# PowerManagementBoard_LabelsAdj.net
KiCad netlist of a schematic drawn in EAGLE
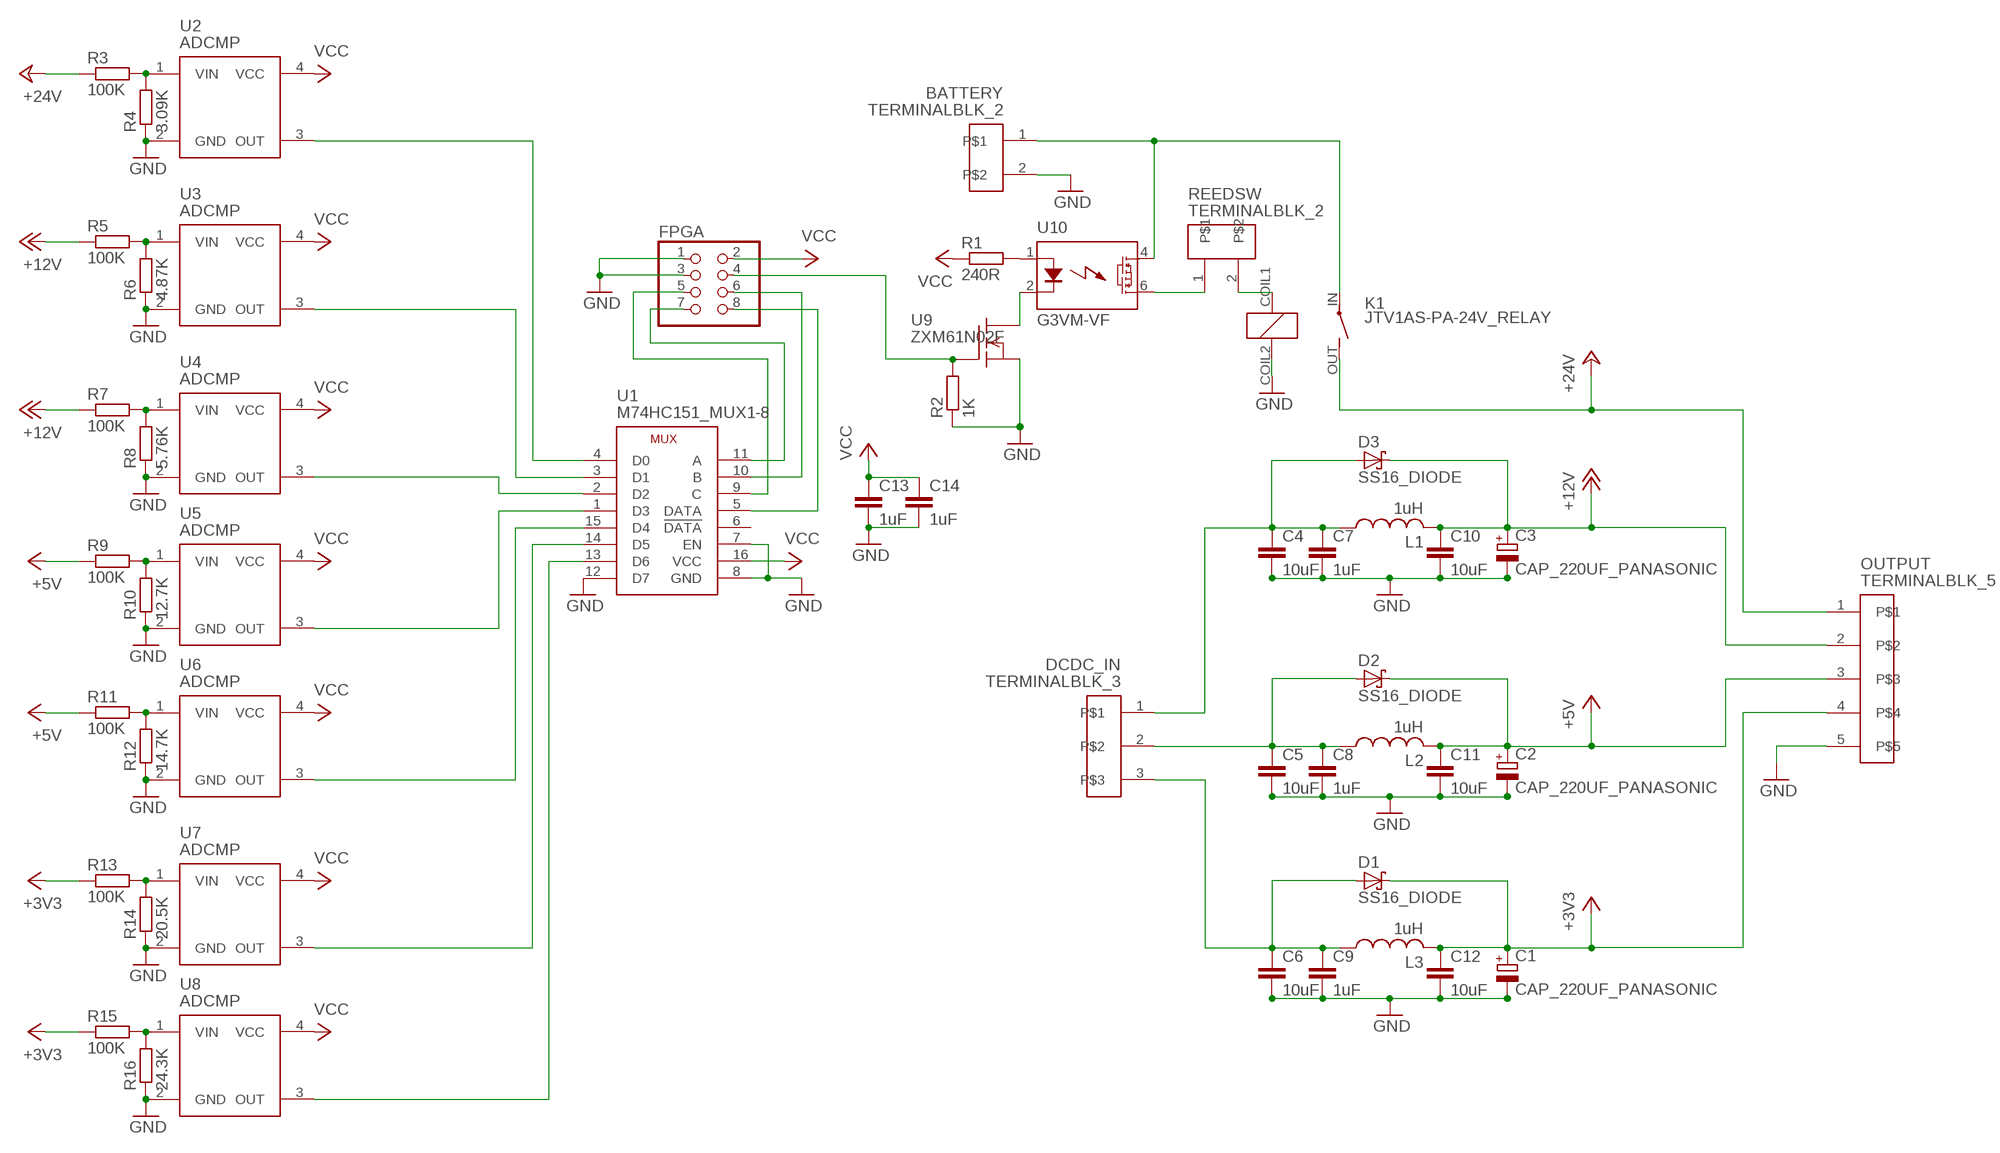
[diagram p0: schematic, sheet 1]

(export (version "E")
  (design (tool "Eeschema 10.0.6"))
  (components
    (comp (ref "BATTERY")
      (value "TERMINALBLK_2")
      (footprint "eagle-import:TERMINAL_BLK-2")
      (libsource (lib "eagle-import") (part "TERMINALBLK_2"))
    )
    (comp (ref "C1")
      (value "CAP_220UF_PANASONIC")
      (footprint "eagle-import:CAP_220UF_PANASONIC")
      (libsource (lib "eagle-import") (part "CAP_220UF_PANASONIC"))
    )
    (comp (ref "C2")
      (value "CAP_220UF_PANASONIC")
      (footprint "eagle-import:CAP_220UF_PANASONIC")
      (libsource (lib "eagle-import") (part "CAP_220UF_PANASONIC"))
    )
    (comp (ref "C3")
      (value "CAP_220UF_PANASONIC")
      (footprint "eagle-import:CAP_220UF_PANASONIC")
      (libsource (lib "eagle-import") (part "CAP_220UF_PANASONIC"))
    )
    (comp (ref "C4")
      (value "10uF")
      (footprint "eagle-import:C1206")
      (libsource (lib "eagle-import") (part "C-EUC1206"))
    )
    (comp (ref "C5")
      (value "10uF")
      (footprint "eagle-import:C1206")
      (libsource (lib "eagle-import") (part "C-EUC1206"))
    )
    (comp (ref "C6")
      (value "10uF")
      (footprint "eagle-import:C1206")
      (libsource (lib "eagle-import") (part "C-EUC1206"))
    )
    (comp (ref "C7")
      (value "1uF")
      (footprint "eagle-import:C1206")
      (libsource (lib "eagle-import") (part "C-EUC1206"))
    )
    (comp (ref "C8")
      (value "1uF")
      (footprint "eagle-import:C1206")
      (libsource (lib "eagle-import") (part "C-EUC1206"))
    )
    (comp (ref "C9")
      (value "1uF")
      (footprint "eagle-import:C1206")
      (libsource (lib "eagle-import") (part "C-EUC1206"))
    )
    (comp (ref "C10")
      (value "10uF")
      (footprint "eagle-import:C1206")
      (libsource (lib "eagle-import") (part "C-EUC1206"))
    )
    (comp (ref "C11")
      (value "10uF")
      (footprint "eagle-import:C1206")
      (libsource (lib "eagle-import") (part "C-EUC1206"))
    )
    (comp (ref "C12")
      (value "10uF")
      (footprint "eagle-import:C1206")
      (libsource (lib "eagle-import") (part "C-EUC1206"))
    )
    (comp (ref "C13")
      (value "1uF")
      (footprint "eagle-import:C1206")
      (libsource (lib "eagle-import") (part "C-EUC1206"))
    )
    (comp (ref "C14")
      (value "1uF")
      (footprint "eagle-import:C1206")
      (libsource (lib "eagle-import") (part "C-EUC1206"))
    )
    (comp (ref "D1")
      (value "SS16_DIODE")
      (footprint "eagle-import:DO214AC")
      (libsource (lib "eagle-import") (part "SS16_DIODE"))
    )
    (comp (ref "D2")
      (value "SS16_DIODE")
      (footprint "eagle-import:DO214AC")
      (libsource (lib "eagle-import") (part "SS16_DIODE"))
    )
    (comp (ref "D3")
      (value "SS16_DIODE")
      (footprint "eagle-import:DO214AC")
      (libsource (lib "eagle-import") (part "SS16_DIODE"))
    )
    (comp (ref "DCDC_IN")
      (value "TERMINALBLK_3")
      (footprint "eagle-import:TERMINAL_BLK-3")
      (libsource (lib "eagle-import") (part "TERMINALBLK_3"))
    )
    (comp (ref "FPGA")
      (value "PINHD-2X4")
      (footprint "eagle-import:2X04")
      (libsource (lib "eagle-import") (part "PINHD-2X4"))
    )
    (comp (ref "K1")
      (value "JTV1AS-PA-24V_RELAY")
      (footprint "eagle-import:JTV-RELAY_FORM1A")
      (libsource (lib "eagle-import") (part "JTV1AS-PA-24V_RELAY"))
    )
    (comp (ref "L1")
      (value "1uH")
      (footprint "eagle-import:CHOKE_WE-HCC_8070")
      (libsource (lib "eagle-import") (part "CHOKE_1UH_WE-HCC_8070"))
    )
    (comp (ref "L2")
      (value "1uH")
      (footprint "eagle-import:CHOKE_WE-HCC_8070")
      (libsource (lib "eagle-import") (part "CHOKE_1UH_WE-HCC_8070"))
    )
    (comp (ref "L3")
      (value "1uH")
      (footprint "eagle-import:CHOKE_WE-HCC_8070")
      (libsource (lib "eagle-import") (part "CHOKE_1UH_WE-HCC_8070"))
    )
    (comp (ref "OUTPUT")
      (value "TERMINALBLK_5")
      (footprint "eagle-import:TERMINAL_BLK-5")
      (libsource (lib "eagle-import") (part "TERMINALBLK_5"))
    )
    (comp (ref "R1")
      (value "240R")
      (footprint "eagle-import:R0603")
      (libsource (lib "eagle-import") (part "R-EU_R0603"))
    )
    (comp (ref "R2")
      (value "1K")
      (footprint "eagle-import:R0603")
      (libsource (lib "eagle-import") (part "R-EU_R0603"))
    )
    (comp (ref "R3")
      (value "100K")
      (footprint "eagle-import:R0603")
      (libsource (lib "eagle-import") (part "R-EU_R0603"))
    )
    (comp (ref "R4")
      (value "3.09K")
      (footprint "eagle-import:R0603")
      (libsource (lib "eagle-import") (part "R-EU_R0603"))
    )
    (comp (ref "R5")
      (value "100K")
      (footprint "eagle-import:R0603")
      (libsource (lib "eagle-import") (part "R-EU_R0603"))
    )
    (comp (ref "R6")
      (value "4.87K")
      (footprint "eagle-import:R0603")
      (libsource (lib "eagle-import") (part "R-EU_R0603"))
    )
    (comp (ref "R7")
      (value "100K")
      (footprint "eagle-import:R0603")
      (libsource (lib "eagle-import") (part "R-EU_R0603"))
    )
    (comp (ref "R8")
      (value "5.76K")
      (footprint "eagle-import:R0603")
      (libsource (lib "eagle-import") (part "R-EU_R0603"))
    )
    (comp (ref "R9")
      (value "100K")
      (footprint "eagle-import:R0603")
      (libsource (lib "eagle-import") (part "R-EU_R0603"))
    )
    (comp (ref "R10")
      (value "12.7K")
      (footprint "eagle-import:R0603")
      (libsource (lib "eagle-import") (part "R-EU_R0603"))
    )
    (comp (ref "R11")
      (value "100K")
      (footprint "eagle-import:R0603")
      (libsource (lib "eagle-import") (part "R-EU_R0603"))
    )
    (comp (ref "R12")
      (value "14.7K")
      (footprint "eagle-import:R0603")
      (libsource (lib "eagle-import") (part "R-EU_R0603"))
    )
    (comp (ref "R13")
      (value "100K")
      (footprint "eagle-import:R0603")
      (libsource (lib "eagle-import") (part "R-EU_R0603"))
    )
    (comp (ref "R14")
      (value "20.5K")
      (footprint "eagle-import:R0603")
      (libsource (lib "eagle-import") (part "R-EU_R0603"))
    )
    (comp (ref "R15")
      (value "100K")
      (footprint "eagle-import:R0603")
      (libsource (lib "eagle-import") (part "R-EU_R0603"))
    )
    (comp (ref "R16")
      (value "24.3K")
      (footprint "eagle-import:R0603")
      (libsource (lib "eagle-import") (part "R-EU_R0603"))
    )
    (comp (ref "REEDSW")
      (value "TERMINALBLK_2")
      (footprint "eagle-import:TERMINAL_BLK-2")
      (libsource (lib "eagle-import") (part "TERMINALBLK_2"))
    )
    (comp (ref "U1")
      (value "M74HC151_MUX1-8")
      (footprint "eagle-import:TSSOP16")
      (libsource (lib "eagle-import") (part "M74HC151_MUX1-8"))
    )
    (comp (ref "U2")
      (value "ADCMP")
      (footprint "eagle-import:SC70-4")
      (libsource (lib "eagle-import") (part "ADCMP"))
    )
    (comp (ref "U3")
      (value "ADCMP")
      (footprint "eagle-import:SC70-4")
      (libsource (lib "eagle-import") (part "ADCMP"))
    )
    (comp (ref "U4")
      (value "ADCMP")
      (footprint "eagle-import:SC70-4")
      (libsource (lib "eagle-import") (part "ADCMP"))
    )
    (comp (ref "U5")
      (value "ADCMP")
      (footprint "eagle-import:SC70-4")
      (libsource (lib "eagle-import") (part "ADCMP"))
    )
    (comp (ref "U6")
      (value "ADCMP")
      (footprint "eagle-import:SC70-4")
      (libsource (lib "eagle-import") (part "ADCMP"))
    )
    (comp (ref "U7")
      (value "ADCMP")
      (footprint "eagle-import:SC70-4")
      (libsource (lib "eagle-import") (part "ADCMP"))
    )
    (comp (ref "U8")
      (value "ADCMP")
      (footprint "eagle-import:SC70-4")
      (libsource (lib "eagle-import") (part "ADCMP"))
    )
    (comp (ref "U9")
      (value "ZXM61N02F")
      (footprint "eagle-import:SOT23W")
      (libsource (lib "eagle-import") (part "ZXM61N02F"))
    )
    (comp (ref "U10")
      (value "G3VM-VF")
      (footprint "eagle-import:G3VM-VF")
      (libsource (lib "eagle-import") (part "G3VM-VF"))
    )
  )
  (nets
    (net (code "1") (name "+3V3") (class "Default")
      (node (ref "C1") (pin "P") (pinfunction "+_P") (pintype "passive"))
      (node (ref "C12") (pin "1") (pinfunction "1_1") (pintype "passive"))
      (node (ref "D1") (pin "C") (pinfunction "C_C") (pintype "passive"))
      (node (ref "L3") (pin "P$2") (pinfunction "2_P$2") (pintype "passive"))
      (node (ref "OUTPUT") (pin "4") (pinfunction "P$4_4") (pintype "bidirectional"))
      (node (ref "R13") (pin "1") (pinfunction "1_1") (pintype "passive"))
      (node (ref "R15") (pin "1") (pinfunction "1_1") (pintype "passive"))
    )
    (net (code "2") (name "+5V") (class "Default")
      (node (ref "C11") (pin "1") (pinfunction "1_1") (pintype "passive"))
      (node (ref "C2") (pin "P") (pinfunction "+_P") (pintype "passive"))
      (node (ref "D2") (pin "C") (pinfunction "C_C") (pintype "passive"))
      (node (ref "L2") (pin "P$2") (pinfunction "2_P$2") (pintype "passive"))
      (node (ref "OUTPUT") (pin "3") (pinfunction "P$3_3") (pintype "bidirectional"))
      (node (ref "R11") (pin "1") (pinfunction "1_1") (pintype "passive"))
      (node (ref "R9") (pin "1") (pinfunction "1_1") (pintype "passive"))
    )
    (net (code "3") (name "+12V") (class "Default")
      (node (ref "C10") (pin "1") (pinfunction "1_1") (pintype "passive"))
      (node (ref "C3") (pin "P") (pinfunction "+_P") (pintype "passive"))
      (node (ref "D3") (pin "C") (pinfunction "C_C") (pintype "passive"))
      (node (ref "L1") (pin "P$2") (pinfunction "2_P$2") (pintype "passive"))
      (node (ref "OUTPUT") (pin "2") (pinfunction "P$2_2") (pintype "bidirectional"))
      (node (ref "R5") (pin "1") (pinfunction "1_1") (pintype "passive"))
      (node (ref "R7") (pin "1") (pinfunction "1_1") (pintype "passive"))
    )
    (net (code "4") (name "+24V") (class "Default")
      (node (ref "K1") (pin "OUT") (pinfunction "S_OUT") (pintype "passive"))
      (node (ref "OUTPUT") (pin "1") (pinfunction "P$1_1") (pintype "bidirectional"))
      (node (ref "R3") (pin "1") (pinfunction "1_1") (pintype "passive"))
    )
    (net (code "5") (name "GND") (class "Default")
      (node (ref "BATTERY") (pin "2") (pinfunction "P$2_2") (pintype "bidirectional"))
      (node (ref "C1") (pin "N") (pinfunction "-_N") (pintype "passive"))
      (node (ref "C10") (pin "2") (pinfunction "2_2") (pintype "passive"))
      (node (ref "C11") (pin "2") (pinfunction "2_2") (pintype "passive"))
      (node (ref "C12") (pin "2") (pinfunction "2_2") (pintype "passive"))
      (node (ref "C13") (pin "2") (pinfunction "2_2") (pintype "passive"))
      (node (ref "C14") (pin "2") (pinfunction "2_2") (pintype "passive"))
      (node (ref "C2") (pin "N") (pinfunction "-_N") (pintype "passive"))
      (node (ref "C3") (pin "N") (pinfunction "-_N") (pintype "passive"))
      (node (ref "C4") (pin "2") (pinfunction "2_2") (pintype "passive"))
      (node (ref "C5") (pin "2") (pinfunction "2_2") (pintype "passive"))
      (node (ref "C6") (pin "2") (pinfunction "2_2") (pintype "passive"))
      (node (ref "C7") (pin "2") (pinfunction "2_2") (pintype "passive"))
      (node (ref "C8") (pin "2") (pinfunction "2_2") (pintype "passive"))
      (node (ref "C9") (pin "2") (pinfunction "2_2") (pintype "passive"))
      (node (ref "FPGA") (pin "1") (pinfunction "1_1") (pintype "passive"))
      (node (ref "FPGA") (pin "3") (pinfunction "3_3") (pintype "passive"))
      (node (ref "K1") (pin "COIL2") (pinfunction "2_COIL2") (pintype "passive"))
      (node (ref "OUTPUT") (pin "5") (pinfunction "P$5_5") (pintype "bidirectional"))
      (node (ref "R10") (pin "1") (pinfunction "1_1") (pintype "passive"))
      (node (ref "R12") (pin "1") (pinfunction "1_1") (pintype "passive"))
      (node (ref "R14") (pin "1") (pinfunction "1_1") (pintype "passive"))
      (node (ref "R16") (pin "1") (pinfunction "1_1") (pintype "passive"))
      (node (ref "R2") (pin "1") (pinfunction "1_1") (pintype "passive"))
      (node (ref "R4") (pin "1") (pinfunction "1_1") (pintype "passive"))
      (node (ref "R6") (pin "1") (pinfunction "1_1") (pintype "passive"))
      (node (ref "R8") (pin "1") (pinfunction "1_1") (pintype "passive"))
      (node (ref "U1") (pin "12") (pinfunction "D7_12") (pintype "bidirectional"))
      (node (ref "U1") (pin "7") (pinfunction "EN_7") (pintype "bidirectional"))
      (node (ref "U1") (pin "8") (pinfunction "GND_8") (pintype "bidirectional"))
      (node (ref "U2") (pin "2") (pinfunction "GND_2") (pintype "bidirectional"))
      (node (ref "U3") (pin "2") (pinfunction "GND_2") (pintype "bidirectional"))
      (node (ref "U4") (pin "2") (pinfunction "GND_2") (pintype "bidirectional"))
      (node (ref "U5") (pin "2") (pinfunction "GND_2") (pintype "bidirectional"))
      (node (ref "U6") (pin "2") (pinfunction "GND_2") (pintype "bidirectional"))
      (node (ref "U7") (pin "2") (pinfunction "GND_2") (pintype "bidirectional"))
      (node (ref "U8") (pin "2") (pinfunction "GND_2") (pintype "bidirectional"))
      (node (ref "U9") (pin "2") (pinfunction "S_2") (pintype "passive"))
    )
    (net (code "6") (name "Net-(BATTERY-P$1)") (class "Default")
      (node (ref "BATTERY") (pin "1") (pinfunction "P$1_1") (pintype "bidirectional"))
      (node (ref "K1") (pin "IN") (pinfunction "P_IN") (pintype "passive"))
      (node (ref "U10") (pin "4") (pinfunction "DS1_4") (pintype "passive"))
    )
    (net (code "7") (name "Net-(DCDC_IN-P$1)") (class "Default")
      (node (ref "C4") (pin "1") (pinfunction "1_1") (pintype "passive"))
      (node (ref "C7") (pin "1") (pinfunction "1_1") (pintype "passive"))
      (node (ref "D3") (pin "A") (pinfunction "A_A") (pintype "passive"))
      (node (ref "DCDC_IN") (pin "1") (pinfunction "P$1_1") (pintype "bidirectional"))
      (node (ref "L1") (pin "P$1") (pinfunction "1_P$1") (pintype "passive"))
    )
    (net (code "8") (name "Net-(DCDC_IN-P$2)") (class "Default")
      (node (ref "C5") (pin "1") (pinfunction "1_1") (pintype "passive"))
      (node (ref "C8") (pin "1") (pinfunction "1_1") (pintype "passive"))
      (node (ref "D2") (pin "A") (pinfunction "A_A") (pintype "passive"))
      (node (ref "DCDC_IN") (pin "2") (pinfunction "P$2_2") (pintype "bidirectional"))
      (node (ref "L2") (pin "P$1") (pinfunction "1_P$1") (pintype "passive"))
    )
    (net (code "9") (name "Net-(DCDC_IN-P$3)") (class "Default")
      (node (ref "C6") (pin "1") (pinfunction "1_1") (pintype "passive"))
      (node (ref "C9") (pin "1") (pinfunction "1_1") (pintype "passive"))
      (node (ref "D1") (pin "A") (pinfunction "A_A") (pintype "passive"))
      (node (ref "DCDC_IN") (pin "3") (pinfunction "P$3_3") (pintype "bidirectional"))
      (node (ref "L3") (pin "P$1") (pinfunction "1_P$1") (pintype "passive"))
    )
    (net (code "10") (name "Net-(K1A-1)") (class "Default")
      (node (ref "K1") (pin "COIL1") (pinfunction "1_COIL1") (pintype "passive"))
      (node (ref "REEDSW") (pin "2") (pinfunction "P$2_2") (pintype "bidirectional"))
    )
    (net (code "11") (name "Net-(REEDSW-P$1)") (class "Default")
      (node (ref "REEDSW") (pin "1") (pinfunction "P$1_1") (pintype "bidirectional"))
      (node (ref "U10") (pin "6") (pinfunction "DS2_6") (pintype "passive"))
    )
    (net (code "12") (name "Net-(U1-A)") (class "Default")
      (node (ref "FPGA") (pin "7") (pinfunction "7_7") (pintype "passive"))
      (node (ref "U1") (pin "11") (pinfunction "A_11") (pintype "bidirectional"))
    )
    (net (code "13") (name "Net-(U1-B)") (class "Default")
      (node (ref "FPGA") (pin "6") (pinfunction "6_6") (pintype "passive"))
      (node (ref "U1") (pin "10") (pinfunction "B_10") (pintype "bidirectional"))
    )
    (net (code "14") (name "Net-(U1-C)") (class "Default")
      (node (ref "FPGA") (pin "5") (pinfunction "5_5") (pintype "passive"))
      (node (ref "U1") (pin "9") (pinfunction "C_9") (pintype "bidirectional"))
    )
    (net (code "15") (name "Net-(U1-D0)") (class "Default")
      (node (ref "U1") (pin "4") (pinfunction "D0_4") (pintype "bidirectional"))
      (node (ref "U2") (pin "3") (pinfunction "OUT_3") (pintype "bidirectional"))
    )
    (net (code "16") (name "Net-(U1-D1)") (class "Default")
      (node (ref "U1") (pin "3") (pinfunction "D1_3") (pintype "bidirectional"))
      (node (ref "U3") (pin "3") (pinfunction "OUT_3") (pintype "bidirectional"))
    )
    (net (code "17") (name "Net-(U1-D2)") (class "Default")
      (node (ref "U1") (pin "2") (pinfunction "D2_2") (pintype "bidirectional"))
      (node (ref "U4") (pin "3") (pinfunction "OUT_3") (pintype "bidirectional"))
    )
    (net (code "18") (name "Net-(U1-D3)") (class "Default")
      (node (ref "U1") (pin "1") (pinfunction "D3_1") (pintype "bidirectional"))
      (node (ref "U5") (pin "3") (pinfunction "OUT_3") (pintype "bidirectional"))
    )
    (net (code "19") (name "Net-(U1-D4)") (class "Default")
      (node (ref "U1") (pin "15") (pinfunction "D4_15") (pintype "bidirectional"))
      (node (ref "U6") (pin "3") (pinfunction "OUT_3") (pintype "bidirectional"))
    )
    (net (code "20") (name "Net-(U1-D5)") (class "Default")
      (node (ref "U1") (pin "14") (pinfunction "D5_14") (pintype "bidirectional"))
      (node (ref "U7") (pin "3") (pinfunction "OUT_3") (pintype "bidirectional"))
    )
    (net (code "21") (name "Net-(U1-D6)") (class "Default")
      (node (ref "U1") (pin "13") (pinfunction "D6_13") (pintype "bidirectional"))
      (node (ref "U8") (pin "3") (pinfunction "OUT_3") (pintype "bidirectional"))
    )
    (net (code "22") (name "Net-(U1-DATA)") (class "Default")
      (node (ref "FPGA") (pin "8") (pinfunction "8_8") (pintype "passive"))
      (node (ref "U1") (pin "5") (pinfunction "DATA_5") (pintype "bidirectional"))
    )
    (net (code "23") (name "Net-(U2-VIN)") (class "Default")
      (node (ref "R3") (pin "2") (pinfunction "2_2") (pintype "passive"))
      (node (ref "R4") (pin "2") (pinfunction "2_2") (pintype "passive"))
      (node (ref "U2") (pin "1") (pinfunction "VIN_1") (pintype "bidirectional"))
    )
    (net (code "24") (name "Net-(U3-VIN)") (class "Default")
      (node (ref "R5") (pin "2") (pinfunction "2_2") (pintype "passive"))
      (node (ref "R6") (pin "2") (pinfunction "2_2") (pintype "passive"))
      (node (ref "U3") (pin "1") (pinfunction "VIN_1") (pintype "bidirectional"))
    )
    (net (code "25") (name "Net-(U4-VIN)") (class "Default")
      (node (ref "R7") (pin "2") (pinfunction "2_2") (pintype "passive"))
      (node (ref "R8") (pin "2") (pinfunction "2_2") (pintype "passive"))
      (node (ref "U4") (pin "1") (pinfunction "VIN_1") (pintype "bidirectional"))
    )
    (net (code "26") (name "Net-(U5-VIN)") (class "Default")
      (node (ref "R10") (pin "2") (pinfunction "2_2") (pintype "passive"))
      (node (ref "R9") (pin "2") (pinfunction "2_2") (pintype "passive"))
      (node (ref "U5") (pin "1") (pinfunction "VIN_1") (pintype "bidirectional"))
    )
    (net (code "27") (name "Net-(U6-VIN)") (class "Default")
      (node (ref "R11") (pin "2") (pinfunction "2_2") (pintype "passive"))
      (node (ref "R12") (pin "2") (pinfunction "2_2") (pintype "passive"))
      (node (ref "U6") (pin "1") (pinfunction "VIN_1") (pintype "bidirectional"))
    )
    (net (code "28") (name "Net-(U7-VIN)") (class "Default")
      (node (ref "R13") (pin "2") (pinfunction "2_2") (pintype "passive"))
      (node (ref "R14") (pin "2") (pinfunction "2_2") (pintype "passive"))
      (node (ref "U7") (pin "1") (pinfunction "VIN_1") (pintype "bidirectional"))
    )
    (net (code "29") (name "Net-(U8-VIN)") (class "Default")
      (node (ref "R15") (pin "2") (pinfunction "2_2") (pintype "passive"))
      (node (ref "R16") (pin "2") (pinfunction "2_2") (pintype "passive"))
      (node (ref "U8") (pin "1") (pinfunction "VIN_1") (pintype "bidirectional"))
    )
    (net (code "30") (name "Net-(U9-G)") (class "Default")
      (node (ref "FPGA") (pin "4") (pinfunction "4_4") (pintype "passive"))
      (node (ref "R2") (pin "2") (pinfunction "2_2") (pintype "passive"))
      (node (ref "U9") (pin "1") (pinfunction "G_1") (pintype "passive"))
    )
    (net (code "31") (name "Net-(U10-A)") (class "Default")
      (node (ref "R1") (pin "2") (pinfunction "2_2") (pintype "passive"))
      (node (ref "U10") (pin "1") (pinfunction "A_1") (pintype "passive"))
    )
    (net (code "32") (name "Net-(U10-K)") (class "Default")
      (node (ref "U10") (pin "2") (pinfunction "K_2") (pintype "passive"))
      (node (ref "U9") (pin "3") (pinfunction "D_3") (pintype "passive"))
    )
    (net (code "33") (name "VCC") (class "Default")
      (node (ref "C13") (pin "1") (pinfunction "1_1") (pintype "passive"))
      (node (ref "C14") (pin "1") (pinfunction "1_1") (pintype "passive"))
      (node (ref "FPGA") (pin "2") (pinfunction "2_2") (pintype "passive"))
      (node (ref "R1") (pin "1") (pinfunction "1_1") (pintype "passive"))
      (node (ref "U1") (pin "16") (pinfunction "VCC_16") (pintype "bidirectional"))
      (node (ref "U2") (pin "4") (pinfunction "VCC_4") (pintype "bidirectional"))
      (node (ref "U3") (pin "4") (pinfunction "VCC_4") (pintype "bidirectional"))
      (node (ref "U4") (pin "4") (pinfunction "VCC_4") (pintype "bidirectional"))
      (node (ref "U5") (pin "4") (pinfunction "VCC_4") (pintype "bidirectional"))
      (node (ref "U6") (pin "4") (pinfunction "VCC_4") (pintype "bidirectional"))
      (node (ref "U7") (pin "4") (pinfunction "VCC_4") (pintype "bidirectional"))
      (node (ref "U8") (pin "4") (pinfunction "VCC_4") (pintype "bidirectional"))
    )
    (net (code "34") (name "unconnected-(U1-~{DATA}-Pad6)") (class "Default")
      (node (ref "U1") (pin "6") (pinfunction "~{DATA}_6") (pintype "bidirectional"))
    )
  )
)
